# Controller.net
KiCad netlist of a schematic drawn in Altium Designer
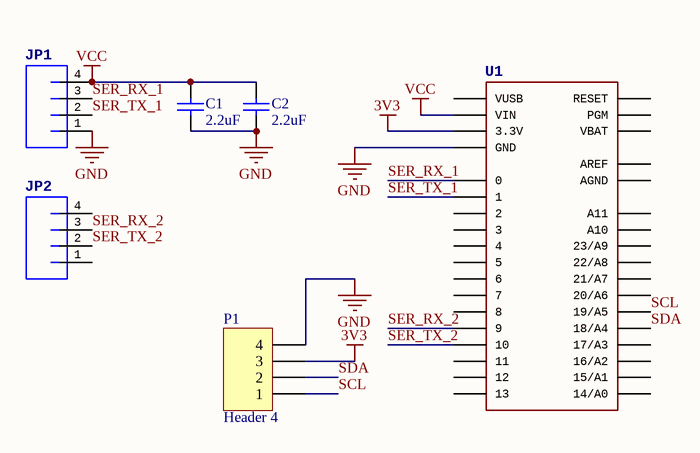
[diagram p0: Controller.SchDoc]

(export (version "E")
  (design (tool "Eeschema 10.0.6"))
  (components
    (comp (ref "C1")
      (value "2.2uF")
      (footprint "CAPC0603(1608)100_L")
      (description "CAP 2.2uF 6.3V ±10% 0603 (1608 Metric) Thickness 1mm SMD")
      (fields (field (name "TOLERANCE") "Â±10%"))
      (libsource (lib "Altium Content Vault") (part "CAP"))
    )
    (comp (ref "C2")
      (value "2.2uF")
      (footprint "CAPC0603(1608)100_L")
      (description "CAP 2.2uF 6.3V ±10% 0603 (1608 Metric) Thickness 1mm SMD")
      (fields (field (name "TOLERANCE") "Â±10%"))
      (libsource (lib "Altium Content Vault") (part "CAP"))
    )
    (comp (ref "JP1")
      (value "~")
      (footprint "JST-4-PTH-VERT")
      (libsource (lib "Components") (part "JST_4_VERT"))
    )
    (comp (ref "JP2")
      (value "~")
      (footprint "JST-4-PTH-VERT")
      (libsource (lib "Components") (part "JST_4_VERT"))
    )
    (comp (ref "P1")
      (value "Header 4")
      (footprint "HDR1X4")
      (description "Header, 4-Pin")
      (fields (field (name "PUBLISHER") "Altium Limited"))
      (libsource (lib "Miscellaneous Connectors") (part "Header 4"))
    )
    (comp (ref "U1")
      (value "~")
      (footprint "TEENSY_3.0+4")
      (libsource (lib "Teensy3.0") (part "TEENSY_3.0+4"))
    )
  )
  (nets
    (net (code "1") (name "/SCL") (class "Default")
      (node (ref "P1") (pin "1") (pinfunction "1_1") (pintype "passive"))
      (node (ref "U1") (pin "19/A5") (pinfunction "19/A5_19/A5") (pintype "passive"))
    )
    (net (code "2") (name "/SDA") (class "Default")
      (node (ref "P1") (pin "2") (pinfunction "2_2") (pintype "passive"))
      (node (ref "U1") (pin "18/A4") (pinfunction "18/A4_18/A4") (pintype "passive"))
    )
    (net (code "3") (name "/SER_RX_1") (class "Default")
      (node (ref "JP1") (pin "3") (pinfunction "3_3") (pintype "passive"))
      (node (ref "U1") (pin "0") (pinfunction "0_0") (pintype "passive"))
    )
    (net (code "4") (name "/SER_RX_2") (class "Default")
      (node (ref "JP2") (pin "3") (pinfunction "3_3") (pintype "passive"))
      (node (ref "U1") (pin "9") (pinfunction "9_9") (pintype "passive"))
    )
    (net (code "5") (name "/SER_TX_1") (class "Default")
      (node (ref "JP1") (pin "2") (pinfunction "2_2") (pintype "passive"))
      (node (ref "U1") (pin "1") (pinfunction "1_1") (pintype "passive"))
    )
    (net (code "6") (name "/SER_TX_2") (class "Default")
      (node (ref "JP2") (pin "2") (pinfunction "2_2") (pintype "passive"))
      (node (ref "U1") (pin "10") (pinfunction "10_10") (pintype "passive"))
    )
    (net (code "7") (name "3V3") (class "Default")
      (node (ref "P1") (pin "3") (pinfunction "3_3") (pintype "passive"))
      (node (ref "U1") (pin "3.3V_3.3V1") (pinfunction "3.3V_3.3V_3.3V1") (pintype "power_in"))
    )
    (net (code "8") (name "GND") (class "Default")
      (node (ref "C1") (pin "1") (pinfunction "1_1") (pintype "passive"))
      (node (ref "C2") (pin "1") (pinfunction "1_1") (pintype "passive"))
      (node (ref "JP1") (pin "1") (pinfunction "1_1") (pintype "passive"))
      (node (ref "P1") (pin "4") (pinfunction "4_4") (pintype "passive"))
      (node (ref "U1") (pin "GND_GND1") (pinfunction "GND_GND_GND1") (pintype "power_in"))
    )
    (net (code "9") (name "VCC") (class "Default")
      (node (ref "C1") (pin "2") (pinfunction "2_2") (pintype "passive"))
      (node (ref "C2") (pin "2") (pinfunction "2_2") (pintype "passive"))
      (node (ref "JP1") (pin "4") (pinfunction "4_4") (pintype "passive"))
      (node (ref "U1") (pin "VIN") (pinfunction "VIN_VIN") (pintype "power_in"))
    )
    (net (code "10") (name "unconnected-(JP2-Pad1)") (class "Default")
      (node (ref "JP2") (pin "1") (pinfunction "1_1") (pintype "passive"))
    )
    (net (code "11") (name "unconnected-(JP2-Pad4)") (class "Default")
      (node (ref "JP2") (pin "4") (pinfunction "4_4") (pintype "passive"))
    )
    (net (code "12") (name "unconnected-(U1-Pad2)") (class "Default")
      (node (ref "U1") (pin "2") (pinfunction "2_2") (pintype "passive"))
    )
    (net (code "13") (name "unconnected-(U1-Pad3)") (class "Default")
      (node (ref "U1") (pin "3") (pinfunction "3_3") (pintype "passive"))
    )
    (net (code "14") (name "unconnected-(U1-Pad4)") (class "Default")
      (node (ref "U1") (pin "4") (pinfunction "4_4") (pintype "passive"))
    )
    (net (code "15") (name "unconnected-(U1-Pad5)") (class "Default")
      (node (ref "U1") (pin "5") (pinfunction "5_5") (pintype "passive"))
    )
    (net (code "16") (name "unconnected-(U1-Pad6)") (class "Default")
      (node (ref "U1") (pin "6") (pinfunction "6_6") (pintype "passive"))
    )
    (net (code "17") (name "unconnected-(U1-Pad7)") (class "Default")
      (node (ref "U1") (pin "7") (pinfunction "7_7") (pintype "passive"))
    )
    (net (code "18") (name "unconnected-(U1-Pad8)") (class "Default")
      (node (ref "U1") (pin "8") (pinfunction "8_8") (pintype "passive"))
    )
    (net (code "19") (name "unconnected-(U1-Pad11)") (class "Default")
      (node (ref "U1") (pin "11") (pinfunction "11_11") (pintype "passive"))
    )
    (net (code "20") (name "unconnected-(U1-Pad12)") (class "Default")
      (node (ref "U1") (pin "12") (pinfunction "12_12") (pintype "passive"))
    )
    (net (code "21") (name "unconnected-(U1-Pad13)") (class "Default")
      (node (ref "U1") (pin "13") (pinfunction "13_13") (pintype "passive"))
    )
    (net (code "22") (name "unconnected-(U1-Pad14{slash}A0)") (class "Default")
      (node (ref "U1") (pin "14/A0") (pinfunction "14/A0_14/A0") (pintype "passive"))
    )
    (net (code "23") (name "unconnected-(U1-Pad15{slash}A1)") (class "Default")
      (node (ref "U1") (pin "15/A1") (pinfunction "15/A1_15/A1") (pintype "passive"))
    )
    (net (code "24") (name "unconnected-(U1-Pad16{slash}A2)") (class "Default")
      (node (ref "U1") (pin "16/A2") (pinfunction "16/A2_16/A2") (pintype "passive"))
    )
    (net (code "25") (name "unconnected-(U1-Pad17{slash}A3)") (class "Default")
      (node (ref "U1") (pin "17/A3") (pinfunction "17/A3_17/A3") (pintype "passive"))
    )
    (net (code "26") (name "unconnected-(U1-Pad20{slash}A6)") (class "Default")
      (node (ref "U1") (pin "20/A6") (pinfunction "20/A6_20/A6") (pintype "passive"))
    )
    (net (code "27") (name "unconnected-(U1-Pad21{slash}A7)") (class "Default")
      (node (ref "U1") (pin "21/A7") (pinfunction "21/A7_21/A7") (pintype "passive"))
    )
    (net (code "28") (name "unconnected-(U1-Pad22{slash}A8)") (class "Default")
      (node (ref "U1") (pin "22/A8") (pinfunction "22/A8_22/A8") (pintype "passive"))
    )
    (net (code "29") (name "unconnected-(U1-Pad23{slash}A9)") (class "Default")
      (node (ref "U1") (pin "23/A9") (pinfunction "23/A9_23/A9") (pintype "passive"))
    )
    (net (code "30") (name "unconnected-(U1-PadA10)") (class "Default")
      (node (ref "U1") (pin "A10") (pinfunction "A10_A10") (pintype "passive"))
    )
    (net (code "31") (name "unconnected-(U1-PadA11)") (class "Default")
      (node (ref "U1") (pin "A11") (pinfunction "A11_A11") (pintype "passive"))
    )
    (net (code "32") (name "unconnected-(U1-PadAGND)") (class "Default")
      (node (ref "U1") (pin "AGND") (pinfunction "AGND_AGND") (pintype "power_in"))
    )
    (net (code "33") (name "unconnected-(U1-PadAREF)") (class "Default")
      (node (ref "U1") (pin "AREF") (pinfunction "AREF_AREF") (pintype "power_in"))
    )
    (net (code "34") (name "unconnected-(U1-PadPGM)") (class "Default")
      (node (ref "U1") (pin "PGM") (pinfunction "PGM_PGM") (pintype "passive"))
    )
    (net (code "35") (name "unconnected-(U1-PadRESET)") (class "Default")
      (node (ref "U1") (pin "RESET") (pinfunction "RESET_RESET") (pintype "passive"))
    )
    (net (code "36") (name "unconnected-(U1-PadVBAT)") (class "Default")
      (node (ref "U1") (pin "VBAT") (pinfunction "VBAT_VBAT") (pintype "power_in"))
    )
    (net (code "37") (name "unconnected-(U1-PadVUSB)") (class "Default")
      (node (ref "U1") (pin "VUSB") (pinfunction "VUSB_VUSB") (pintype "power_in"))
    )
  )
)
